# PCEmon_PLUS_rev_B.net
KiCad netlist of a schematic drawn in EAGLE
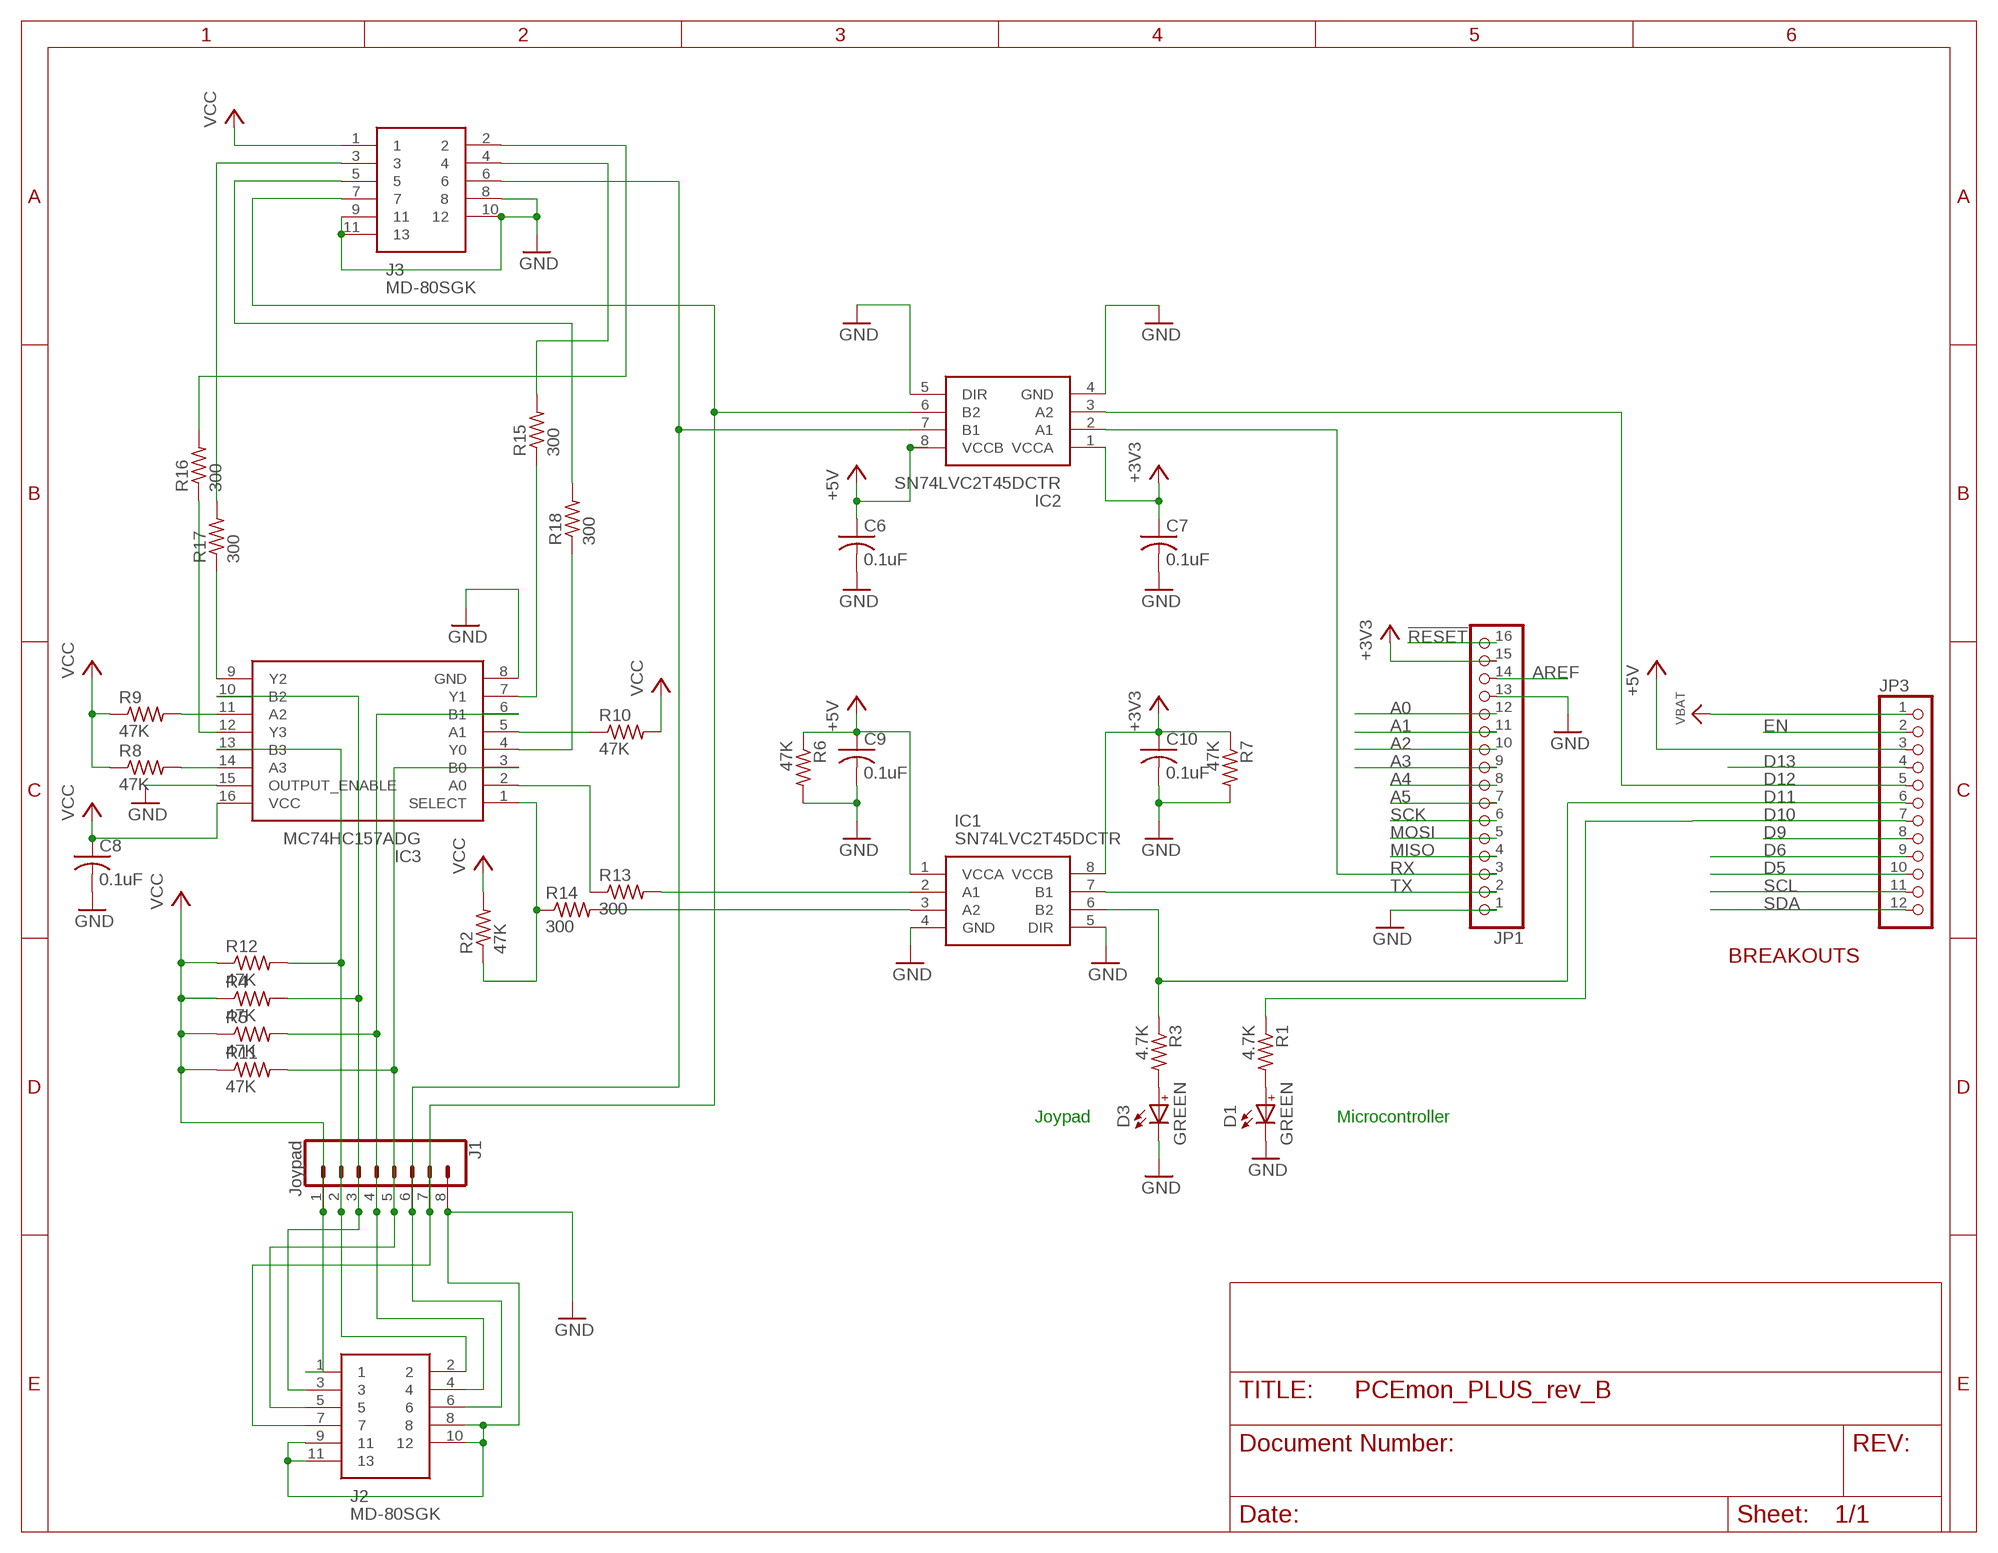
[diagram p0: schematic, sheet 1]

(export (version "E")
  (design (tool "Eeschema 10.0.6"))
  (components
    (comp (ref "C6")
      (value "0.1uF")
      (footprint "eagle-import:C0603")
      (libsource (lib "eagle-import") (part "C-USC0603"))
    )
    (comp (ref "C7")
      (value "0.1uF")
      (footprint "eagle-import:C0603")
      (libsource (lib "eagle-import") (part "C-USC0603"))
    )
    (comp (ref "C8")
      (value "0.1uF")
      (footprint "eagle-import:C0603")
      (libsource (lib "eagle-import") (part "C-USC0603"))
    )
    (comp (ref "C9")
      (value "0.1uF")
      (footprint "eagle-import:C0603")
      (libsource (lib "eagle-import") (part "C-USC0603"))
    )
    (comp (ref "C10")
      (value "0.1uF")
      (footprint "eagle-import:C0603")
      (libsource (lib "eagle-import") (part "C-USC0603"))
    )
    (comp (ref "D1")
      (value "GREEN")
      (footprint "eagle-import:WL-SMCC_0603_R_Y_V")
      (libsource (lib "eagle-import") (part "WL-SMCC_0603_R/V/Y_150060RS73220"))
    )
    (comp (ref "D3")
      (value "GREEN")
      (footprint "eagle-import:WL-SMCC_0603_R_Y_V")
      (libsource (lib "eagle-import") (part "WL-SMCC_0603_R/V/Y_150060RS73220"))
    )
    (comp (ref "IC1")
      (value "SN74LVC2T45DCTR")
      (footprint "eagle-import:SOP65P400X130-8N")
      (fields
        (field (name "MOUSER_PART_NUMBER") "595-SN74LVC2T45DCTR")
        (field (name "RS_PART_NUMBER") "9213022")
      )
      (libsource (lib "eagle-import") (part "SN74LVC2T45DCTR"))
    )
    (comp (ref "IC2")
      (value "SN74LVC2T45DCTR")
      (footprint "eagle-import:SOP65P400X130-8N")
      (fields
        (field (name "MOUSER_PART_NUMBER") "595-SN74LVC2T45DCTR")
        (field (name "RS_PART_NUMBER") "9213022")
      )
      (libsource (lib "eagle-import") (part "SN74LVC2T45DCTR"))
    )
    (comp (ref "IC3")
      (value "MC74HC157ADG")
      (footprint "eagle-import:SOIC127P600X175-16N")
      (fields
        (field (name "MOUSER_PART_NUMBER") "863-MC74HC157ADG")
        (field (name "RS_PART_NUMBER") "8061422P")
      )
      (libsource (lib "eagle-import") (part "MC74HC157ADG"))
    )
    (comp (ref "J1")
      (value "Joypad")
      (footprint "eagle-import:1X08")
      (libsource (lib "eagle-import") (part "CONN_08{dblquote}"))
    )
    (comp (ref "J2")
      (value "MD-80SGK")
      (footprint "eagle-import:MD80SGK")
      (fields (field (name "MOUSER_PART_NUMBER") "490-MD-80SGK"))
      (libsource (lib "eagle-import") (part "MD-80SGK"))
    )
    (comp (ref "J3")
      (value "MD-80SGK")
      (footprint "eagle-import:MD80SGK")
      (fields (field (name "MOUSER_PART_NUMBER") "490-MD-80SGK"))
      (libsource (lib "eagle-import") (part "MD-80SGK"))
    )
    (comp (ref "JP1")
      (value "HEADER-1X16ROUND")
      (footprint "eagle-import:1X16_ROUND")
      (libsource (lib "eagle-import") (part "HEADER-1X16ROUND"))
    )
    (comp (ref "JP3")
      (value "HEADER-1X12")
      (footprint "eagle-import:1X12_ROUND")
      (libsource (lib "eagle-import") (part "HEADER-1X12"))
    )
    (comp (ref "R1")
      (value "4.7K")
      (footprint "eagle-import:R0603")
      (libsource (lib "eagle-import") (part "R-US_R0603"))
    )
    (comp (ref "R2")
      (value "47K")
      (footprint "eagle-import:R0603")
      (libsource (lib "eagle-import") (part "R-US_R0603"))
    )
    (comp (ref "R3")
      (value "4.7K")
      (footprint "eagle-import:R0603")
      (libsource (lib "eagle-import") (part "R-US_R0603"))
    )
    (comp (ref "R4")
      (value "47K")
      (footprint "eagle-import:R0603")
      (libsource (lib "eagle-import") (part "R-US_R0603"))
    )
    (comp (ref "R5")
      (value "47K")
      (footprint "eagle-import:R0603")
      (libsource (lib "eagle-import") (part "R-US_R0603"))
    )
    (comp (ref "R6")
      (value "47K")
      (footprint "eagle-import:R0603")
      (libsource (lib "eagle-import") (part "R-US_R0603"))
    )
    (comp (ref "R7")
      (value "47K")
      (footprint "eagle-import:R0603")
      (libsource (lib "eagle-import") (part "R-US_R0603"))
    )
    (comp (ref "R8")
      (value "47K")
      (footprint "eagle-import:R0603")
      (libsource (lib "eagle-import") (part "R-US_R0603"))
    )
    (comp (ref "R9")
      (value "47K")
      (footprint "eagle-import:R0603")
      (libsource (lib "eagle-import") (part "R-US_R0603"))
    )
    (comp (ref "R10")
      (value "47K")
      (footprint "eagle-import:R0603")
      (libsource (lib "eagle-import") (part "R-US_R0603"))
    )
    (comp (ref "R11")
      (value "47K")
      (footprint "eagle-import:R0603")
      (libsource (lib "eagle-import") (part "R-US_R0603"))
    )
    (comp (ref "R12")
      (value "47K")
      (footprint "eagle-import:R0603")
      (libsource (lib "eagle-import") (part "R-US_R0603"))
    )
    (comp (ref "R13")
      (value "300")
      (footprint "eagle-import:R0603")
      (libsource (lib "eagle-import") (part "R-US_R0603"))
    )
    (comp (ref "R14")
      (value "300")
      (footprint "eagle-import:R0603")
      (libsource (lib "eagle-import") (part "R-US_R0603"))
    )
    (comp (ref "R15")
      (value "300")
      (footprint "eagle-import:R0603")
      (libsource (lib "eagle-import") (part "R-US_R0603"))
    )
    (comp (ref "R16")
      (value "300")
      (footprint "eagle-import:R0603")
      (libsource (lib "eagle-import") (part "R-US_R0603"))
    )
    (comp (ref "R17")
      (value "300")
      (footprint "eagle-import:R0603")
      (libsource (lib "eagle-import") (part "R-US_R0603"))
    )
    (comp (ref "R18")
      (value "300")
      (footprint "eagle-import:R0603")
      (libsource (lib "eagle-import") (part "R-US_R0603"))
    )
  )
  (nets
    (net (code "1") (name "+3V3") (class "Default")
      (node (ref "C10") (pin "1") (pinfunction "1_1") (pintype "passive"))
      (node (ref "C7") (pin "1") (pinfunction "1_1") (pintype "passive"))
      (node (ref "IC1") (pin "8") (pinfunction "VCCB_8") (pintype "power_in"))
      (node (ref "IC2") (pin "1") (pinfunction "VCCA_1") (pintype "power_in"))
      (node (ref "JP1") (pin "15") (pinfunction "15_15") (pintype "passive"))
      (node (ref "R7") (pin "1") (pinfunction "1_1") (pintype "passive"))
    )
    (net (code "2") (name "+5V") (class "Default")
      (node (ref "C6") (pin "1") (pinfunction "1_1") (pintype "passive"))
      (node (ref "C9") (pin "1") (pinfunction "1_1") (pintype "passive"))
      (node (ref "IC1") (pin "1") (pinfunction "VCCA_1") (pintype "power_in"))
      (node (ref "IC2") (pin "8") (pinfunction "VCCB_8") (pintype "power_in"))
      (node (ref "JP3") (pin "3") (pinfunction "3_3") (pintype "passive"))
      (node (ref "R6") (pin "1") (pinfunction "1_1") (pintype "passive"))
    )
    (net (code "3") (name "/A0") (class "Default")
      (node (ref "JP1") (pin "12") (pinfunction "12_12") (pintype "passive"))
    )
    (net (code "4") (name "/A1") (class "Default")
      (node (ref "JP1") (pin "11") (pinfunction "11_11") (pintype "passive"))
    )
    (net (code "5") (name "/A2") (class "Default")
      (node (ref "JP1") (pin "10") (pinfunction "10_10") (pintype "passive"))
    )
    (net (code "6") (name "/A3") (class "Default")
      (node (ref "JP1") (pin "9") (pinfunction "9_9") (pintype "passive"))
    )
    (net (code "7") (name "/A4") (class "Default")
      (node (ref "JP1") (pin "8") (pinfunction "8_8") (pintype "passive"))
    )
    (net (code "8") (name "/A5") (class "Default")
      (node (ref "JP1") (pin "7") (pinfunction "7_7") (pintype "passive"))
    )
    (net (code "9") (name "/AREF") (class "Default")
      (node (ref "JP1") (pin "14") (pinfunction "14_14") (pintype "passive"))
    )
    (net (code "10") (name "/D5") (class "Default")
      (node (ref "JP3") (pin "10") (pinfunction "10_10") (pintype "passive"))
    )
    (net (code "11") (name "/D6") (class "Default")
      (node (ref "JP3") (pin "9") (pinfunction "9_9") (pintype "passive"))
    )
    (net (code "12") (name "/D9") (class "Default")
      (node (ref "JP3") (pin "8") (pinfunction "8_8") (pintype "passive"))
    )
    (net (code "13") (name "/D10") (class "Default")
      (node (ref "JP3") (pin "7") (pinfunction "7_7") (pintype "passive"))
      (node (ref "R1") (pin "1") (pinfunction "1_1") (pintype "passive"))
    )
    (net (code "14") (name "/D11") (class "Default")
      (node (ref "IC1") (pin "6") (pinfunction "B2_6") (pintype "bidirectional"))
      (node (ref "JP3") (pin "6") (pinfunction "6_6") (pintype "passive"))
      (node (ref "R3") (pin "1") (pinfunction "1_1") (pintype "passive"))
    )
    (net (code "15") (name "/D12") (class "Default")
      (node (ref "IC2") (pin "3") (pinfunction "A2_3") (pintype "bidirectional"))
      (node (ref "JP3") (pin "5") (pinfunction "5_5") (pintype "passive"))
    )
    (net (code "16") (name "/D13") (class "Default")
      (node (ref "JP3") (pin "4") (pinfunction "4_4") (pintype "passive"))
    )
    (net (code "17") (name "/EN") (class "Default")
      (node (ref "JP3") (pin "2") (pinfunction "2_2") (pintype "passive"))
    )
    (net (code "18") (name "/MISO") (class "Default")
      (node (ref "JP1") (pin "4") (pinfunction "4_4") (pintype "passive"))
    )
    (net (code "19") (name "/MOSI") (class "Default")
      (node (ref "JP1") (pin "5") (pinfunction "5_5") (pintype "passive"))
    )
    (net (code "20") (name "/RX") (class "Default")
      (node (ref "IC2") (pin "2") (pinfunction "A1_2") (pintype "bidirectional"))
      (node (ref "JP1") (pin "3") (pinfunction "3_3") (pintype "passive"))
    )
    (net (code "21") (name "/SCK") (class "Default")
      (node (ref "JP1") (pin "6") (pinfunction "6_6") (pintype "passive"))
    )
    (net (code "22") (name "/SCL") (class "Default")
      (node (ref "JP3") (pin "11") (pinfunction "11_11") (pintype "passive"))
    )
    (net (code "23") (name "/SDA") (class "Default")
      (node (ref "JP3") (pin "12") (pinfunction "12_12") (pintype "passive"))
    )
    (net (code "24") (name "/TX") (class "Default")
      (node (ref "IC1") (pin "7") (pinfunction "B1_7") (pintype "bidirectional"))
      (node (ref "JP1") (pin "2") (pinfunction "2_2") (pintype "passive"))
    )
    (net (code "25") (name "/~{RESET}") (class "Default")
      (node (ref "JP1") (pin "16") (pinfunction "16_16") (pintype "passive"))
    )
    (net (code "26") (name "GND") (class "Default")
      (node (ref "C10") (pin "2") (pinfunction "2_2") (pintype "passive"))
      (node (ref "C6") (pin "2") (pinfunction "2_2") (pintype "passive"))
      (node (ref "C7") (pin "2") (pinfunction "2_2") (pintype "passive"))
      (node (ref "C8") (pin "2") (pinfunction "2_2") (pintype "passive"))
      (node (ref "C9") (pin "2") (pinfunction "2_2") (pintype "passive"))
      (node (ref "D1") (pin "1") (pinfunction "C_1") (pintype "passive"))
      (node (ref "D3") (pin "1") (pinfunction "C_1") (pintype "passive"))
      (node (ref "IC1") (pin "4") (pinfunction "GND_4") (pintype "power_in"))
      (node (ref "IC1") (pin "5") (pinfunction "DIR_5") (pintype "bidirectional"))
      (node (ref "IC2") (pin "4") (pinfunction "GND_4") (pintype "power_in"))
      (node (ref "IC2") (pin "5") (pinfunction "DIR_5") (pintype "bidirectional"))
      (node (ref "IC3") (pin "15") (pinfunction "OUTPUT_ENABLE_15") (pintype "input"))
      (node (ref "IC3") (pin "8") (pinfunction "GND_8") (pintype "power_in"))
      (node (ref "J1") (pin "8") (pinfunction "8_8") (pintype "passive"))
      (node (ref "J2") (pin "10") (pinfunction "12_10") (pintype "bidirectional"))
      (node (ref "J2") (pin "11") (pinfunction "13_11") (pintype "bidirectional"))
      (node (ref "J2") (pin "8") (pinfunction "8_8") (pintype "bidirectional"))
      (node (ref "J2") (pin "9") (pinfunction "11_9") (pintype "bidirectional"))
      (node (ref "J3") (pin "10") (pinfunction "12_10") (pintype "bidirectional"))
      (node (ref "J3") (pin "11") (pinfunction "13_11") (pintype "bidirectional"))
      (node (ref "J3") (pin "8") (pinfunction "8_8") (pintype "bidirectional"))
      (node (ref "J3") (pin "9") (pinfunction "11_9") (pintype "bidirectional"))
      (node (ref "JP1") (pin "1") (pinfunction "1_1") (pintype "passive"))
      (node (ref "JP1") (pin "13") (pinfunction "13_13") (pintype "passive"))
      (node (ref "R6") (pin "2") (pinfunction "2_2") (pintype "passive"))
      (node (ref "R7") (pin "2") (pinfunction "2_2") (pintype "passive"))
    )
    (net (code "27") (name "Net-(D1-A)") (class "Default")
      (node (ref "D1") (pin "2") (pinfunction "A_2") (pintype "passive"))
      (node (ref "R1") (pin "2") (pinfunction "2_2") (pintype "passive"))
    )
    (net (code "28") (name "Net-(D3-A)") (class "Default")
      (node (ref "D3") (pin "2") (pinfunction "A_2") (pintype "passive"))
      (node (ref "R3") (pin "2") (pinfunction "2_2") (pintype "passive"))
    )
    (net (code "29") (name "Net-(IC1-A1)") (class "Default")
      (node (ref "IC1") (pin "2") (pinfunction "A1_2") (pintype "bidirectional"))
      (node (ref "R13") (pin "2") (pinfunction "2_2") (pintype "passive"))
    )
    (net (code "30") (name "Net-(IC1-A2)") (class "Default")
      (node (ref "IC1") (pin "3") (pinfunction "A2_3") (pintype "bidirectional"))
      (node (ref "R14") (pin "2") (pinfunction "2_2") (pintype "passive"))
    )
    (net (code "31") (name "Net-(IC2-B1)") (class "Default")
      (node (ref "IC2") (pin "7") (pinfunction "B1_7") (pintype "bidirectional"))
      (node (ref "J1") (pin "6") (pinfunction "6_6") (pintype "passive"))
      (node (ref "J2") (pin "6") (pinfunction "6_6") (pintype "bidirectional"))
      (node (ref "J3") (pin "6") (pinfunction "6_6") (pintype "bidirectional"))
    )
    (net (code "32") (name "Net-(IC2-B2)") (class "Default")
      (node (ref "IC2") (pin "6") (pinfunction "B2_6") (pintype "bidirectional"))
      (node (ref "J1") (pin "7") (pinfunction "7_7") (pintype "passive"))
      (node (ref "J2") (pin "7") (pinfunction "7_7") (pintype "bidirectional"))
      (node (ref "J3") (pin "7") (pinfunction "7_7") (pintype "bidirectional"))
    )
    (net (code "33") (name "Net-(IC3-A0)") (class "Default")
      (node (ref "IC3") (pin "2") (pinfunction "A0_2") (pintype "input"))
      (node (ref "R13") (pin "1") (pinfunction "1_1") (pintype "passive"))
    )
    (net (code "34") (name "Net-(IC3-A1)") (class "Default")
      (node (ref "IC3") (pin "5") (pinfunction "A1_5") (pintype "input"))
      (node (ref "R10") (pin "1") (pinfunction "1_1") (pintype "passive"))
    )
    (net (code "35") (name "Net-(IC3-A2)") (class "Default")
      (node (ref "IC3") (pin "11") (pinfunction "A2_11") (pintype "input"))
      (node (ref "R9") (pin "2") (pinfunction "2_2") (pintype "passive"))
    )
    (net (code "36") (name "Net-(IC3-A3)") (class "Default")
      (node (ref "IC3") (pin "14") (pinfunction "A3_14") (pintype "input"))
      (node (ref "R8") (pin "2") (pinfunction "2_2") (pintype "passive"))
    )
    (net (code "37") (name "Net-(IC3-B0)") (class "Default")
      (node (ref "IC3") (pin "3") (pinfunction "B0_3") (pintype "input"))
      (node (ref "J1") (pin "5") (pinfunction "5_5") (pintype "passive"))
      (node (ref "J2") (pin "5") (pinfunction "5_5") (pintype "bidirectional"))
      (node (ref "R11") (pin "2") (pinfunction "2_2") (pintype "passive"))
    )
    (net (code "38") (name "Net-(IC3-B1)") (class "Default")
      (node (ref "IC3") (pin "6") (pinfunction "B1_6") (pintype "input"))
      (node (ref "J1") (pin "4") (pinfunction "4_4") (pintype "passive"))
      (node (ref "J2") (pin "4") (pinfunction "4_4") (pintype "bidirectional"))
      (node (ref "R5") (pin "2") (pinfunction "2_2") (pintype "passive"))
    )
    (net (code "39") (name "Net-(IC3-B2)") (class "Default")
      (node (ref "IC3") (pin "10") (pinfunction "B2_10") (pintype "input"))
      (node (ref "J1") (pin "3") (pinfunction "3_3") (pintype "passive"))
      (node (ref "J2") (pin "3") (pinfunction "3_3") (pintype "bidirectional"))
      (node (ref "R4") (pin "2") (pinfunction "2_2") (pintype "passive"))
    )
    (net (code "40") (name "Net-(IC3-B3)") (class "Default")
      (node (ref "IC3") (pin "13") (pinfunction "B3_13") (pintype "input"))
      (node (ref "J1") (pin "2") (pinfunction "2_2") (pintype "passive"))
      (node (ref "J2") (pin "2") (pinfunction "2_2") (pintype "bidirectional"))
      (node (ref "R12") (pin "2") (pinfunction "2_2") (pintype "passive"))
    )
    (net (code "41") (name "Net-(IC3-SELECT)") (class "Default")
      (node (ref "IC3") (pin "1") (pinfunction "SELECT_1") (pintype "input"))
      (node (ref "R14") (pin "1") (pinfunction "1_1") (pintype "passive"))
      (node (ref "R2") (pin "1") (pinfunction "1_1") (pintype "passive"))
    )
    (net (code "42") (name "Net-(IC3-Y0)") (class "Default")
      (node (ref "IC3") (pin "4") (pinfunction "Y0_4") (pintype "output"))
      (node (ref "R18") (pin "1") (pinfunction "1_1") (pintype "passive"))
    )
    (net (code "43") (name "Net-(IC3-Y1)") (class "Default")
      (node (ref "IC3") (pin "7") (pinfunction "Y1_7") (pintype "output"))
      (node (ref "R15") (pin "1") (pinfunction "1_1") (pintype "passive"))
    )
    (net (code "44") (name "Net-(IC3-Y2)") (class "Default")
      (node (ref "IC3") (pin "9") (pinfunction "Y2_9") (pintype "output"))
      (node (ref "R17") (pin "1") (pinfunction "1_1") (pintype "passive"))
    )
    (net (code "45") (name "Net-(IC3-Y3)") (class "Default")
      (node (ref "IC3") (pin "12") (pinfunction "Y3_12") (pintype "output"))
      (node (ref "R16") (pin "1") (pinfunction "1_1") (pintype "passive"))
    )
    (net (code "46") (name "Net-(J3-Pad2)") (class "Default")
      (node (ref "J3") (pin "2") (pinfunction "2_2") (pintype "bidirectional"))
      (node (ref "R16") (pin "2") (pinfunction "2_2") (pintype "passive"))
    )
    (net (code "47") (name "Net-(J3-Pad3)") (class "Default")
      (node (ref "J3") (pin "3") (pinfunction "3_3") (pintype "bidirectional"))
      (node (ref "R17") (pin "2") (pinfunction "2_2") (pintype "passive"))
    )
    (net (code "48") (name "Net-(J3-Pad4)") (class "Default")
      (node (ref "J3") (pin "4") (pinfunction "4_4") (pintype "bidirectional"))
      (node (ref "R15") (pin "2") (pinfunction "2_2") (pintype "passive"))
    )
    (net (code "49") (name "Net-(J3-Pad5)") (class "Default")
      (node (ref "J3") (pin "5") (pinfunction "5_5") (pintype "bidirectional"))
      (node (ref "R18") (pin "2") (pinfunction "2_2") (pintype "passive"))
    )
    (net (code "50") (name "VBAT") (class "Default")
      (node (ref "JP3") (pin "1") (pinfunction "1_1") (pintype "passive"))
    )
    (net (code "51") (name "VCC") (class "Default")
      (node (ref "C8") (pin "1") (pinfunction "1_1") (pintype "passive"))
      (node (ref "IC3") (pin "16") (pinfunction "VCC_16") (pintype "power_in"))
      (node (ref "J1") (pin "1") (pinfunction "1_1") (pintype "passive"))
      (node (ref "J2") (pin "1") (pinfunction "1_1") (pintype "bidirectional"))
      (node (ref "J3") (pin "1") (pinfunction "1_1") (pintype "bidirectional"))
      (node (ref "R10") (pin "2") (pinfunction "2_2") (pintype "passive"))
      (node (ref "R11") (pin "1") (pinfunction "1_1") (pintype "passive"))
      (node (ref "R12") (pin "1") (pinfunction "1_1") (pintype "passive"))
      (node (ref "R2") (pin "2") (pinfunction "2_2") (pintype "passive"))
      (node (ref "R4") (pin "1") (pinfunction "1_1") (pintype "passive"))
      (node (ref "R5") (pin "1") (pinfunction "1_1") (pintype "passive"))
      (node (ref "R8") (pin "1") (pinfunction "1_1") (pintype "passive"))
      (node (ref "R9") (pin "1") (pinfunction "1_1") (pintype "passive"))
    )
  )
)
